# 555-dev.net
KiCad netlist of a schematic drawn in EAGLE
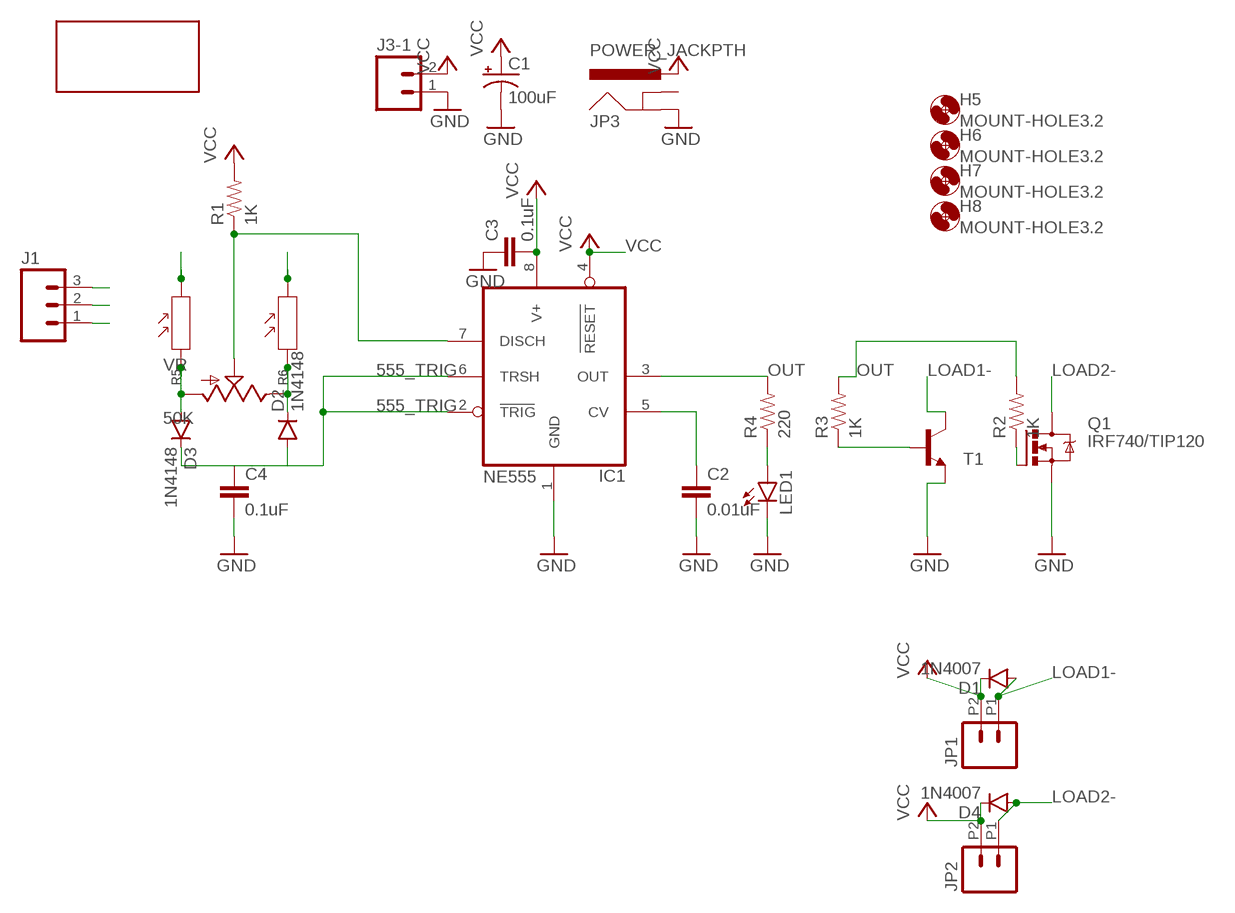
[diagram p0: schematic, sheet 1]

(export (version "E")
  (design (tool "Eeschema 10.0.6"))
  (components
    (comp (ref "C1")
      (value "100uF")
      (footprint "eagle-import:CPOL-RADIAL-100UF-25V")
      (libsource (lib "eagle-import") (part "CAP_POLPTH1"))
    )
    (comp (ref "C2")
      (value "0.01uF")
      (footprint "eagle-import:CAP-PTH-5MM")
      (libsource (lib "eagle-import") (part "CAPPTH1"))
    )
    (comp (ref "C3")
      (value "0.1uF")
      (footprint "eagle-import:CAP-PTH-5MM")
      (libsource (lib "eagle-import") (part "CAPPTH1"))
    )
    (comp (ref "C4")
      (value "0.1uF")
      (footprint "eagle-import:CAP-PTH-5MM")
      (libsource (lib "eagle-import") (part "CAPPTH1"))
    )
    (comp (ref "D1")
      (value "1N4007")
      (footprint "eagle-import:DIODE-1N4148-KIT")
      (libsource (lib "eagle-import") (part "DIODEKIT"))
    )
    (comp (ref "D2")
      (value "1N4148")
      (footprint "eagle-import:DIODE-1N4148")
      (libsource (lib "eagle-import") (part "DIODE1N4148"))
    )
    (comp (ref "D3")
      (value "1N4148")
      (footprint "eagle-import:DIODE-1N4148")
      (libsource (lib "eagle-import") (part "DIODE1N4148"))
    )
    (comp (ref "D4")
      (value "1N4007")
      (footprint "eagle-import:DIODE-1N4148-KIT")
      (libsource (lib "eagle-import") (part "DIODEKIT"))
    )
    (comp (ref "H5")
      (value "MOUNT-HOLE3.2")
      (footprint "eagle-import:3,2")
      (libsource (lib "eagle-import") (part "MOUNT-HOLE3.2"))
    )
    (comp (ref "H6")
      (value "MOUNT-HOLE3.2")
      (footprint "eagle-import:3,2")
      (libsource (lib "eagle-import") (part "MOUNT-HOLE3.2"))
    )
    (comp (ref "H7")
      (value "MOUNT-HOLE3.2")
      (footprint "eagle-import:3,2")
      (libsource (lib "eagle-import") (part "MOUNT-HOLE3.2"))
    )
    (comp (ref "H8")
      (value "MOUNT-HOLE3.2")
      (footprint "eagle-import:3,2")
      (libsource (lib "eagle-import") (part "MOUNT-HOLE3.2"))
    )
    (comp (ref "IC1")
      (value "NE555")
      (footprint "eagle-import:DIL08")
      (libsource (lib "eagle-import") (part "TLC555"))
    )
    (comp (ref "J1")
      (value "M03PTH")
      (footprint "eagle-import:1X03")
      (libsource (lib "eagle-import") (part "M03PTH"))
    )
    (comp (ref "J3-1")
      (value "M02PTH")
      (footprint "eagle-import:1X02")
      (libsource (lib "eagle-import") (part "M02PTH"))
    )
    (comp (ref "JP1")
      (value "M022.54MM_SCREWTERM")
      (footprint "eagle-import:1X02_2.54_SCREWTERM")
      (libsource (lib "eagle-import") (part "M022.54MM_SCREWTERM"))
    )
    (comp (ref "JP2")
      (value "M022.54MM_SCREWTERM")
      (footprint "eagle-import:1X02_2.54_SCREWTERM")
      (libsource (lib "eagle-import") (part "M022.54MM_SCREWTERM"))
    )
    (comp (ref "JP3")
      (value "POWER_JACKPTH")
      (footprint "eagle-import:POWER_JACK_PTH")
      (libsource (lib "eagle-import") (part "POWER_JACKPTH"))
    )
    (comp (ref "LED1")
      (value "LED5MM-KIT")
      (footprint "eagle-import:LED5MM-KIT")
      (libsource (lib "eagle-import") (part "LED5MM-KIT"))
    )
    (comp (ref "Q1")
      (value "IRF740/TIP120")
      (footprint "eagle-import:TO220BV")
      (libsource (lib "eagle-import") (part "IRF740"))
    )
    (comp (ref "R1")
      (value "1K")
      (footprint "eagle-import:AXIAL-0.4")
      (libsource (lib "eagle-import") (part "RESISTORPTH-1/4W"))
    )
    (comp (ref "R2")
      (value "1K")
      (footprint "eagle-import:AXIAL-0.4")
      (libsource (lib "eagle-import") (part "RESISTORPTH-1/4W"))
    )
    (comp (ref "R3")
      (value "1K")
      (footprint "eagle-import:AXIAL-0.4")
      (libsource (lib "eagle-import") (part "RESISTORPTH-1/4W"))
    )
    (comp (ref "R4")
      (value "220")
      (footprint "eagle-import:AXIAL-0.4")
      (libsource (lib "eagle-import") (part "RESISTORPTH-1/4W"))
    )
    (comp (ref "R5")
      (value "R-PHOTOVARISTOR'0546'")
      (footprint "eagle-import:0546_3.3")
      (libsource (lib "eagle-import") (part "R-PHOTOVARISTOR'0546'"))
    )
    (comp (ref "R6")
      (value "R-PHOTOVARISTOR'0546'")
      (footprint "eagle-import:0546_3.3")
      (libsource (lib "eagle-import") (part "R-PHOTOVARISTOR'0546'"))
    )
    (comp (ref "T1")
      (value "2N2222")
      (footprint "eagle-import:TO92-EBC-OVAL")
      (libsource (lib "eagle-import") (part "2N2222"))
    )
    (comp (ref "U$1")
      (value "LOGO")
      (footprint "eagle-import:LOGO")
      (libsource (lib "eagle-import") (part "LOGO"))
    )
    (comp (ref "VR")
      (value "50K")
      (footprint "eagle-import:ALPS_POT_KIT")
      (libsource (lib "eagle-import") (part "POTALPS-KIT"))
    )
  )
  (nets
    (net (code "1") (name "/555_DISCH") (class "Default")
      (node (ref "IC1") (pin "7") (pinfunction "DISCH_7") (pintype "input"))
      (node (ref "J1") (pin "2") (pinfunction "2_2") (pintype "passive"))
      (node (ref "R1") (pin "P$1") (pinfunction "1_P$1") (pintype "passive"))
      (node (ref "VR") (pin "P$2") (pinfunction "S_P$2") (pintype "passive"))
    )
    (net (code "2") (name "/555_TRIG") (class "Default")
      (node (ref "C4") (pin "1") (pinfunction "1_1") (pintype "passive"))
      (node (ref "D2") (pin "A") (pinfunction "A_A") (pintype "passive"))
      (node (ref "D3") (pin "C") (pinfunction "C_C") (pintype "passive"))
      (node (ref "IC1") (pin "2") (pinfunction "TRIG_2") (pintype "bidirectional"))
      (node (ref "IC1") (pin "6") (pinfunction "TRSH_6") (pintype "input"))
    )
    (net (code "3") (name "/LOAD1-") (class "Default")
      (node (ref "D1") (pin "A") (pinfunction "A_A") (pintype "passive"))
      (node (ref "JP1") (pin "P1") (pinfunction "1_P1") (pintype "passive"))
      (node (ref "T1") (pin "C") (pinfunction "C_C") (pintype "passive"))
    )
    (net (code "4") (name "/LOAD2-") (class "Default")
      (node (ref "D4") (pin "A") (pinfunction "A_A") (pintype "passive"))
      (node (ref "JP2") (pin "P1") (pinfunction "1_P1") (pintype "passive"))
      (node (ref "Q1") (pin "D") (pinfunction "D_D") (pintype "passive"))
    )
    (net (code "5") (name "/OUT") (class "Default")
      (node (ref "IC1") (pin "3") (pinfunction "OUT_3") (pintype "output"))
      (node (ref "R2") (pin "P$2") (pinfunction "2_P$2") (pintype "passive"))
      (node (ref "R3") (pin "P$2") (pinfunction "2_P$2") (pintype "passive"))
      (node (ref "R4") (pin "P$2") (pinfunction "2_P$2") (pintype "passive"))
    )
    (net (code "6") (name "/PR1") (class "Default")
      (node (ref "J1") (pin "1") (pinfunction "1_1") (pintype "passive"))
      (node (ref "R5") (pin "P$2") (pinfunction "P$2_P$2") (pintype "bidirectional"))
    )
    (net (code "7") (name "/PR2") (class "Default")
      (node (ref "J1") (pin "3") (pinfunction "3_3") (pintype "passive"))
      (node (ref "R6") (pin "P$2") (pinfunction "P$2_P$2") (pintype "bidirectional"))
    )
    (net (code "8") (name "GND") (class "Default")
      (node (ref "C1") (pin "2") (pinfunction "-_2") (pintype "passive"))
      (node (ref "C2") (pin "2") (pinfunction "2_2") (pintype "passive"))
      (node (ref "C3") (pin "1") (pinfunction "1_1") (pintype "passive"))
      (node (ref "C4") (pin "2") (pinfunction "2_2") (pintype "passive"))
      (node (ref "IC1") (pin "1") (pinfunction "GND_1") (pintype "power_in"))
      (node (ref "J3-1") (pin "1") (pinfunction "1_1") (pintype "passive"))
      (node (ref "JP3") (pin "GND") (pinfunction "GND_GND") (pintype "bidirectional"))
      (node (ref "LED1") (pin "K") (pinfunction "C_K") (pintype "passive"))
      (node (ref "Q1") (pin "S") (pinfunction "S_S") (pintype "passive"))
      (node (ref "T1") (pin "E") (pinfunction "E_E") (pintype "passive"))
    )
    (net (code "9") (name "Net-(IC1-CV)") (class "Default")
      (node (ref "C2") (pin "1") (pinfunction "1_1") (pintype "passive"))
      (node (ref "IC1") (pin "5") (pinfunction "CV_5") (pintype "passive"))
    )
    (net (code "10") (name "Net-(R2-1)") (class "Default")
      (node (ref "Q1") (pin "G") (pinfunction "G_G") (pintype "passive"))
      (node (ref "R2") (pin "P$1") (pinfunction "1_P$1") (pintype "passive"))
    )
    (net (code "11") (name "Net-(R3-1)") (class "Default")
      (node (ref "R3") (pin "P$1") (pinfunction "1_P$1") (pintype "passive"))
      (node (ref "T1") (pin "B") (pinfunction "B_B") (pintype "passive"))
    )
    (net (code "12") (name "Net-(R4-1)") (class "Default")
      (node (ref "LED1") (pin "A") (pinfunction "A_A") (pintype "passive"))
      (node (ref "R4") (pin "P$1") (pinfunction "1_P$1") (pintype "passive"))
    )
    (net (code "13") (name "Net-(VR-A)") (class "Default")
      (node (ref "D3") (pin "A") (pinfunction "A_A") (pintype "passive"))
      (node (ref "R5") (pin "P$1") (pinfunction "P$1_P$1") (pintype "bidirectional"))
      (node (ref "VR") (pin "P$3") (pinfunction "A_P$3") (pintype "passive"))
    )
    (net (code "14") (name "Net-(VR-E)") (class "Default")
      (node (ref "D2") (pin "C") (pinfunction "C_C") (pintype "passive"))
      (node (ref "R6") (pin "P$1") (pinfunction "P$1_P$1") (pintype "bidirectional"))
      (node (ref "VR") (pin "P$1") (pinfunction "E_P$1") (pintype "passive"))
    )
    (net (code "15") (name "VCC") (class "Default")
      (node (ref "C1") (pin "1") (pinfunction "+_1") (pintype "passive"))
      (node (ref "C3") (pin "2") (pinfunction "2_2") (pintype "passive"))
      (node (ref "D1") (pin "C") (pinfunction "C_C") (pintype "passive"))
      (node (ref "D4") (pin "C") (pinfunction "C_C") (pintype "passive"))
      (node (ref "IC1") (pin "4") (pinfunction "RESET_4") (pintype "input"))
      (node (ref "IC1") (pin "8") (pinfunction "V+_8") (pintype "power_in"))
      (node (ref "J3-1") (pin "2") (pinfunction "2_2") (pintype "passive"))
      (node (ref "JP1") (pin "P2") (pinfunction "2_P2") (pintype "passive"))
      (node (ref "JP2") (pin "P2") (pinfunction "2_P2") (pintype "passive"))
      (node (ref "JP3") (pin "PWR") (pinfunction "PWR_PWR") (pintype "bidirectional"))
      (node (ref "R1") (pin "P$2") (pinfunction "2_P$2") (pintype "passive"))
    )
    (net (code "16") (name "unconnected-(JP3-PadGNDBREAK)") (class "Default")
      (node (ref "JP3") (pin "GNDBREAK") (pinfunction "GNDBREAK_GNDBREAK") (pintype "bidirectional"))
    )
  )
)
